# CWStage.net
KiCad netlist of a schematic drawn in Altium Designer
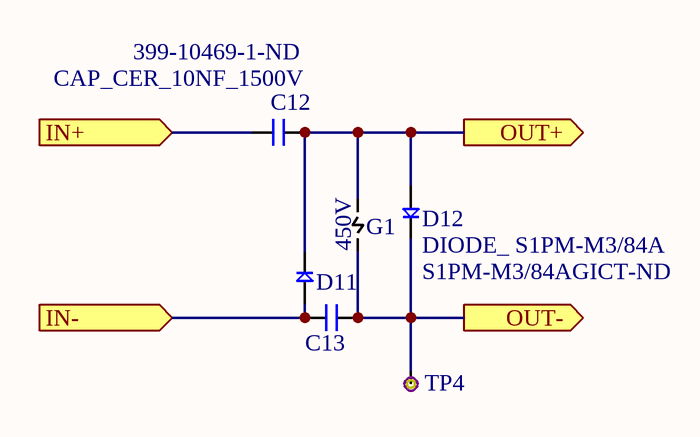
[diagram p0: CWStage.SchDoc]

(export (version "E")
  (design (tool "Eeschema 10.0.6"))
  (components
    (comp (ref "C12")
      (value "CAP_CER_10NF_1500V")
      (footprint "C1206")
      (fields (field (name "SUPPLIER PART NUMBER 1") "399-10469-1-ND"))
      (libsource (lib "SSI") (part "CAP_CER_10NF_1500V"))
    )
    (comp (ref "C13")
      (value "CAP_CER_10NF_1500V")
      (footprint "C1206")
      (libsource (lib "SSI") (part "CAP_CER_10NF_1500V"))
    )
    (comp (ref "D11")
      (value "DIODE_ S1PM-M3/84A")
      (footprint "DO-220AA")
      (libsource (lib "SSI") (part "DIODE_ S1PM-M3/84A"))
    )
    (comp (ref "D12")
      (value "DIODE_ S1PM-M3/84A")
      (footprint "DO-220AA")
      (fields (field (name "SUPPLIER PART NUMBER 1") "S1PM-M3/84AGICT-ND"))
      (libsource (lib "SSI") (part "DIODE_ S1PM-M3/84A"))
    )
    (comp (ref "G1")
      (value "450V")
      (footprint "SPARK_GAP_450V")
      (libsource (lib "SSI") (part "SPARK_GAP_450V"))
    )
    (comp (ref "TP4")
      (value "TEST_POINT_PURPLE_KEYSTONE_5119")
      (footprint "TEST_POINT_KEYSTONE_5119")
      (description "PURPLE T/H TEST POINT")
      (fields
        (field (name "MANUFACTURER") "Keystone Electronics")
        (field (name "MANUFACTURER PART NUMBER") "5119")
      )
      (libsource (lib "SSI") (part "TEST_POINT_PURPLE_KEYSTONE_5119"))
    )
  )
  (nets
    (net (code "1") (name "/IN+") (class "Default") (node (ref "C12") (pin "1") (pintype "passive")))
    (net (code "2") (name "/IN-") (class "Default")
      (node (ref "C13") (pin "1") (pintype "passive"))
      (node (ref "D11") (pin "2") (pintype "passive"))
    )
    (net (code "3") (name "/OUT+") (class "Default")
      (node (ref "C12") (pin "2") (pintype "passive"))
      (node (ref "D11") (pin "1") (pintype "passive"))
      (node (ref "D12") (pin "2") (pintype "passive"))
      (node (ref "G1") (pin "2") (pinfunction "2_2") (pintype "power_in"))
    )
    (net (code "4") (name "/OUT-") (class "Default")
      (node (ref "C13") (pin "2") (pintype "passive"))
      (node (ref "D12") (pin "1") (pintype "passive"))
      (node (ref "G1") (pin "1") (pinfunction "1_1") (pintype "power_in"))
      (node (ref "TP4") (pin "1") (pinfunction "1_1") (pintype "passive"))
    )
  )
)
